# ADC.net
KiCad netlist of a schematic drawn in Altium Designer
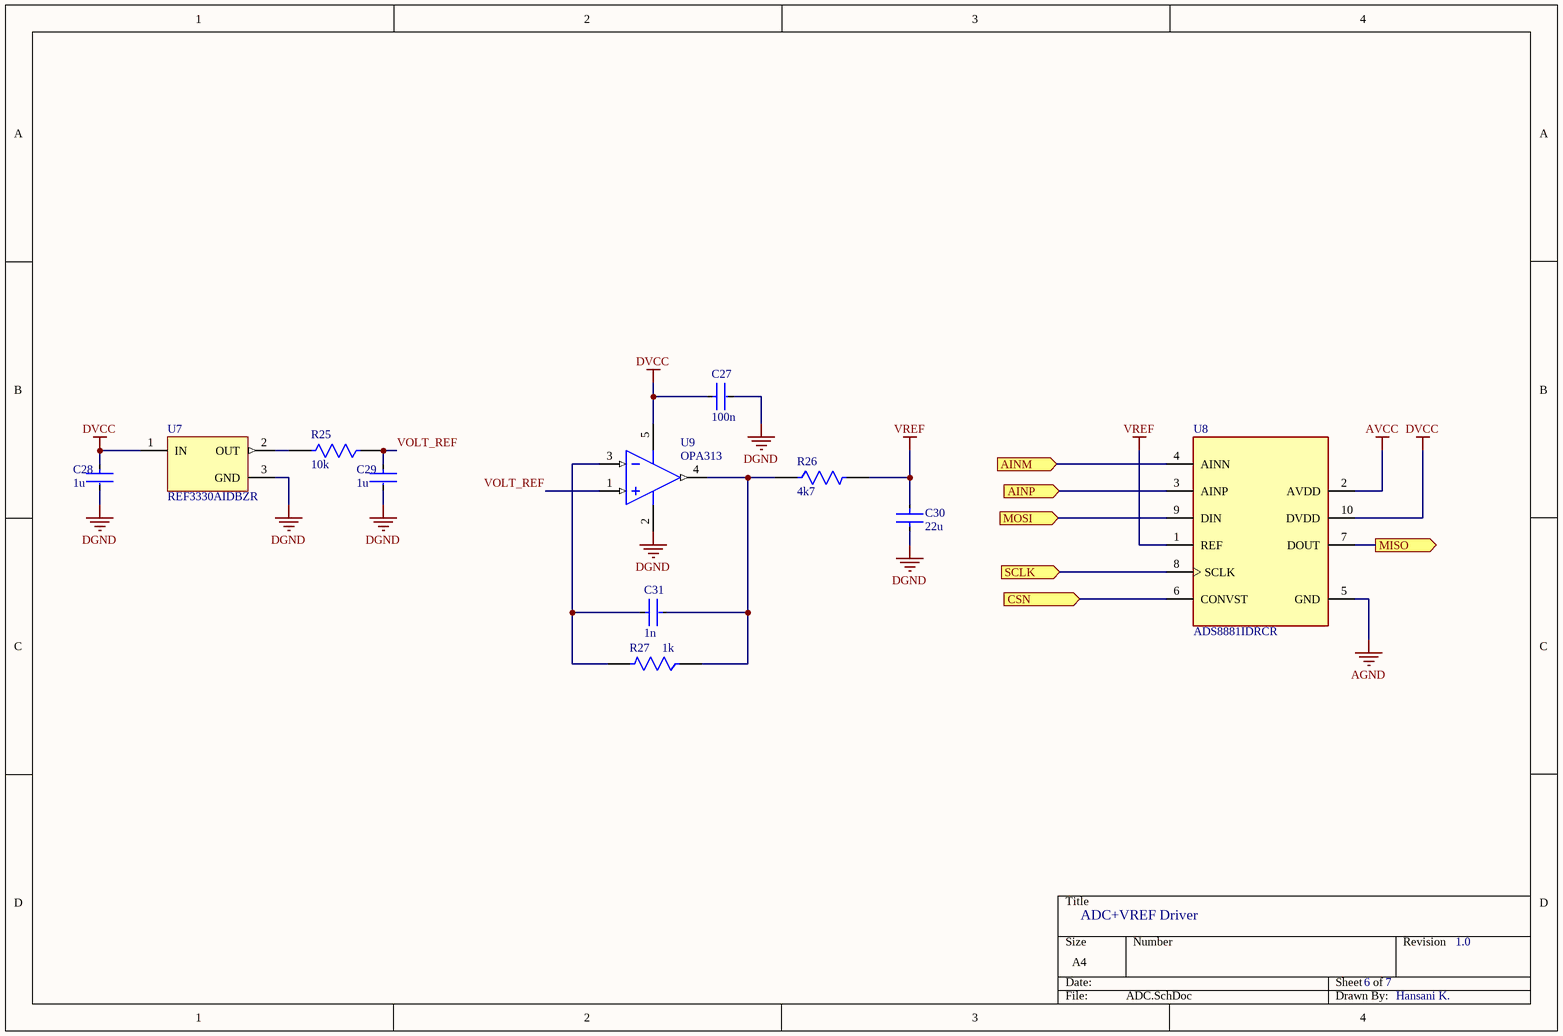
[diagram p0: ADC.SchDoc]

(export (version "E")
  (design (tool "Eeschema 10.0.6"))
  (components
    (comp (ref "C27")
      (value "100n")
      (footprint "FP-GRM155-0_05-MFG")
      (description "Chip Multilayer Ceramic Capacitors for General Purpose, 0402, 0.10uF, B, 10%, 20%, 50V")
      (libsource (lib "Altium Content Vault") (part "02cd4be3c70576c341d710602a673aa"))
    )
    (comp (ref "C28")
      (value "1u")
      (footprint "FP-0603-L_1_6_0_15-W_0_81-IPC_A")
      (description "General Purpose Ceramic Capacitor, 0603, 1uF, 10%, X5R, 15%, 6.3V")
      (fields (field (name "VOLTAGE") "6.3V") (field (name "TOLERANCE") "10%"))
      (libsource (lib "Altium Content Vault") (part "02cd4be3c70576c341d710602a673aa"))
    )
    (comp (ref "C29")
      (value "1u")
      (footprint "FP-0603-L_1_6_0_15-W_0_81-IPC_A")
      (description "General Purpose Ceramic Capacitor, 0603, 1uF, 10%, X5R, 15%, 6.3V")
      (fields (field (name "VOLTAGE") "6.3V") (field (name "TOLERANCE") "10%"))
      (libsource (lib "Altium Content Vault") (part "02cd4be3c70576c341d710602a673aa"))
    )
    (comp (ref "C30")
      (value "22u")
      (footprint "PCBComponent_1")
      (fields
        (field (name "MANUFACTURER") "Samsung Electro-Mechanics")
        (field (name "MANUFACTURER PART NUMBER") "CL21A226MAYNNNE")
        (field (name "TOLERANCE") "20%")
      )
      (libsource (lib "Schlib1") (part "CL21A226MAYNNNE"))
    )
    (comp (ref "C31")
      (value "1n")
      (footprint "PCBComponent_1")
      (fields
        (field (name "MANUFACTURER") "Yageo Group")
        (field (name "MANUFACTURER PART NUMBER") "CS0805KRX7RBBB102")
        (field (name "TOLERANCE") "10%")
      )
      (libsource (lib "Schlib1") (part "CS0805KRX7RBBB102"))
    )
    (comp (ref "R25")
      (value "10k")
      (footprint "FP-CRGCQ0805-IPC_C")
      (description "CRGCQ 0805 10K 5%")
      (fields
        (field (name "MANUFACTURER PART NUMBER") "CRGCQ0805J10K")
        (field (name "MANUFACTURER") "TE Connectivity")
      )
      (libsource (lib "Altium Content Vault") (part "1029c3af85768c4190bb7ad29bc67b5"))
    )
    (comp (ref "R26")
      (value "4k7")
      (footprint "FP-RN73R2A-IPC_C")
      (description "4.7kΩ ±0.1% 0.125W, 1/8W Chip Resistor 0805 (2012 Metric) Moisture Resistant Thin Film")
      (libsource (lib "Altium Content Vault") (part "1029c3af85768c4190bb7ad29bc67b5"))
    )
    (comp (ref "R27")
      (value "1k")
      (footprint "FP-PATT0805-MFG")
      (description "RES SMD 1K OHM 0.1% 1/5W 0805")
      (fields (field (name "TOLERANCE") "0.1%") (field (name "MANUFACTURER PART NUMBER") "PATT0805E1001BGT1"))
      (libsource (lib "Altium Content Vault") (part "1029c3af85768c4190bb7ad29bc67b5"))
    )
    (comp (ref "U7")
      (value "REF3330AIDBZR")
      (footprint "DBZ0003A_L")
      (fields (field (name "MANUFACTURER") "Texas Instruments"))
      (libsource (lib "Altium Content Vault") (part "TI-REF3330DBZ3"))
    )
    (comp (ref "U8")
      (value "ADS8881IDRCR")
      (footprint "ADS8881IDRCR")
      (description "IC ADC 18BIT SAR 10VSON 18 Bit Analog to Digital Converter 1 Input 1 SAR 10-VSON (3x3)")
      (fields (field (name "MANUFACTURER") "Texas Instruments"))
      (libsource (lib "Schlib1") (part "ADS8881IDRCR"))
    )
    (comp (ref "U9")
      (value "OPA313")
      (footprint "DCK0005A_L")
      (fields (field (name "MANUFACTURER") "Texas Instruments") (field (name "PARTNUMBER") "OPA313IDCKR"))
      (libsource (lib "Altium Content Vault") (part "TI-OPA313-DCK5"))
    )
  )
  (nets
    (net (code "1") (name "/AINM") (class "Default")
      (node (ref "U8") (pin "4") (pinfunction "AINN_4") (pintype "passive"))
    )
    (net (code "2") (name "/AINP") (class "Default")
      (node (ref "U8") (pin "3") (pinfunction "AINP_3") (pintype "passive"))
    )
    (net (code "3") (name "/CSN") (class "Default")
      (node (ref "U8") (pin "6") (pinfunction "CONVST_6") (pintype "passive"))
    )
    (net (code "4") (name "/MISO") (class "Default")
      (node (ref "U8") (pin "7") (pinfunction "DOUT_7") (pintype "passive"))
    )
    (net (code "5") (name "/MOSI") (class "Default")
      (node (ref "U8") (pin "9") (pinfunction "DIN_9") (pintype "passive"))
    )
    (net (code "6") (name "/SCLK") (class "Default")
      (node (ref "U8") (pin "8") (pinfunction "SCLK_8") (pintype "passive"))
    )
    (net (code "7") (name "/VOLT_REF") (class "Default")
      (node (ref "C29") (pin "1") (pinfunction "1_1") (pintype "passive"))
      (node (ref "R25") (pin "1") (pinfunction "1_1") (pintype "passive"))
      (node (ref "U9") (pin "1") (pinfunction "IN+_1") (pintype "input"))
    )
    (net (code "8") (name "AGND") (class "Default")
      (node (ref "U8") (pin "5") (pinfunction "GND_5") (pintype "passive"))
    )
    (net (code "9") (name "AVCC") (class "Default")
      (node (ref "U8") (pin "2") (pinfunction "AVDD_2") (pintype "passive"))
    )
    (net (code "10") (name "DGND") (class "Default")
      (node (ref "C27") (pin "2") (pinfunction "2_2") (pintype "passive"))
      (node (ref "C28") (pin "2") (pinfunction "2_2") (pintype "passive"))
      (node (ref "C29") (pin "2") (pinfunction "2_2") (pintype "passive"))
      (node (ref "C30") (pin "1") (pinfunction "1_1") (pintype "passive"))
      (node (ref "U7") (pin "3") (pinfunction "GND_3") (pintype "power_in"))
      (node (ref "U9") (pin "2") (pinfunction "V-_2") (pintype "power_in"))
    )
    (net (code "11") (name "DVCC") (class "Default")
      (node (ref "C27") (pin "1") (pinfunction "1_1") (pintype "passive"))
      (node (ref "C28") (pin "1") (pinfunction "1_1") (pintype "passive"))
      (node (ref "U7") (pin "1") (pinfunction "IN_1") (pintype "power_in"))
      (node (ref "U8") (pin "10") (pinfunction "DVDD_10") (pintype "passive"))
      (node (ref "U9") (pin "5") (pinfunction "V+_5") (pintype "power_in"))
    )
    (net (code "12") (name "Net-(U7-OUT)") (class "Default")
      (node (ref "R25") (pin "2") (pinfunction "2_2") (pintype "passive"))
      (node (ref "U7") (pin "2") (pinfunction "OUT_2") (pintype "output"))
    )
    (net (code "13") (name "Net-(U9-IN-)") (class "Default")
      (node (ref "C31") (pin "1") (pinfunction "1_1") (pintype "passive"))
      (node (ref "R27") (pin "2") (pinfunction "2_2") (pintype "passive"))
      (node (ref "U9") (pin "3") (pinfunction "IN-_3") (pintype "input"))
    )
    (net (code "14") (name "Net-(U9-OUT)") (class "Default")
      (node (ref "C31") (pin "2") (pinfunction "2_2") (pintype "passive"))
      (node (ref "R26") (pin "1") (pinfunction "1_1") (pintype "passive"))
      (node (ref "R27") (pin "1") (pinfunction "1_1") (pintype "passive"))
      (node (ref "U9") (pin "4") (pinfunction "OUT_4") (pintype "output"))
    )
    (net (code "15") (name "VREF") (class "Default")
      (node (ref "C30") (pin "2") (pinfunction "2_2") (pintype "passive"))
      (node (ref "R26") (pin "2") (pinfunction "2_2") (pintype "passive"))
      (node (ref "U8") (pin "1") (pinfunction "REF_1") (pintype "passive"))
    )
  )
)
